# Step-down_converter.net
KiCad netlist of a schematic drawn in Altium Designer
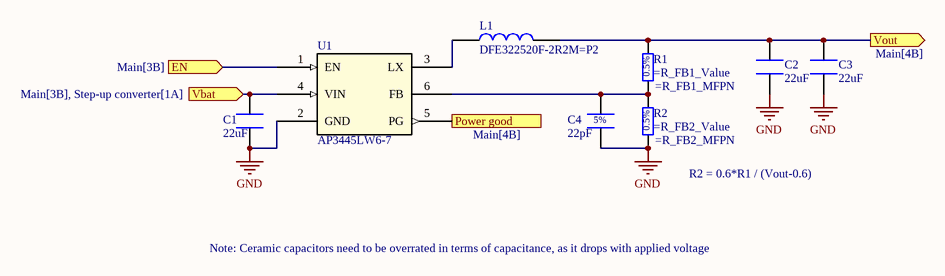
[diagram p0: Step-down converter.SchDoc]

(export (version "E")
  (design (tool "Eeschema 10.0.6"))
  (components
    (comp (ref "C1")
      (value "22uF")
      (footprint "APSS Prototype Parts:CAPACITOR_0805_2012M-70N")
      (description "Passive - Capacitor, X5R, 22uF Max, 6.3V, 0805 (2012 Metric), ±20%, -55°C ~ 85°C. 8.8uF @ 5V")
      (fields (field (name "TOLERANCE") "±20%") (field (name "MF PART NO.") "C0805C226M9PACTU"))
      (libsource (lib "APSS Prototype Parts") (part "C0805C226M9PACTU"))
    )
    (comp (ref "C2")
      (value "22uF")
      (footprint "APSS Prototype Parts:CAPACITOR_0805_2012M-70N")
      (description "Passive - Capacitor, X5R, 22uF Max, 6.3V, 0805 (2012 Metric), ±20%, -55°C ~ 85°C. 8.8uF @ 5V")
      (fields (field (name "TOLERANCE") "±20%") (field (name "MF PART NO.") "C0805C226M9PACTU"))
      (libsource (lib "APSS Prototype Parts") (part "C0805C226M9PACTU"))
    )
    (comp (ref "C3")
      (value "22uF")
      (footprint "APSS Prototype Parts:CAPACITOR_0805_2012M-70N")
      (description "Passive - Capacitor, X5R, 22uF Max, 6.3V, 0805 (2012 Metric), ±20%, -55°C ~ 85°C. 8.8uF @ 5V")
      (fields (field (name "TOLERANCE") "±20%") (field (name "MF PART NO.") "C0805C226M9PACTU"))
      (libsource (lib "APSS Prototype Parts") (part "C0805C226M9PACTU"))
    )
    (comp (ref "C4")
      (value "22pF")
      (footprint "APSS Generic Components:CAPACITOR_0805_2012M-70N")
      (description "Generic Capacitor")
      (fields (field (name "TOLERANCE") "5%") (field (name "MF PART NO.") "C0805C220J5GACTU"))
      (libsource (lib "APSS Generic Components") (part "Generic Capacitor"))
    )
    (comp (ref "L1")
      (value "DFE322520F-2R2M=P2")
      (footprint "INDC3225X200N")
      (description "2.2 uH Shielded Wirewound Inductor 3.3 A 40mOhm Max 1210 (3225 Metric)")
      (libsource (lib "DFE322520F-2R2M=P2") (part "DFE322520F-2R2M=P2"))
    )
    (comp (ref "R1")
      (value "~")
      (footprint "APSS Flight Parts:Resistor_0805_2012M-50N")
      (fields
        (field (name "TOLERANCE") "0.5%")
        (field (name "POWER") "1/8W")
        (field (name "APSS STANDARD PART") "APSS Standard")
      )
      (libsource (lib "APSS Prototype Parts") (part "RG2012P-xxx-D-T5 Series"))
    )
    (comp (ref "R2")
      (value "~")
      (footprint "APSS Flight Parts:Resistor_0805_2012M-50N")
      (fields
        (field (name "TOLERANCE") "0.5%")
        (field (name "POWER") "1/8W")
        (field (name "APSS STANDARD PART") "APSS Standard")
      )
      (libsource (lib "APSS Prototype Parts") (part "RG2012P-xxx-D-T5 Series"))
    )
    (comp (ref "U1")
      (value "AP3445LW6-7")
      (footprint "APSS Prototype Parts:SOT23-6N-1.4mm")
      (description "IC - Regulator, Buck, 2A, 2.7V to 5.5V In, 0.6V to Vin Out, SOT23-6")
      (fields (field (name "APSS STANDARD PART") "APSS Standard"))
      (libsource (lib "APSS Prototype Parts") (part "AP3445LW6-7"))
    )
  )
  (nets
    (net (code "1") (name "/EN") (class "Default")
      (node (ref "U1") (pin "1") (pinfunction "EN_1") (pintype "input"))
    )
    (net (code "2") (name "/Power good") (class "Default")
      (node (ref "U1") (pin "5") (pinfunction "PG_5") (pintype "output"))
    )
    (net (code "3") (name "/Vbat") (class "Default")
      (node (ref "C1") (pin "2") (pinfunction "2_2") (pintype "passive"))
      (node (ref "U1") (pin "4") (pinfunction "VIN_4") (pintype "input"))
    )
    (net (code "4") (name "/Vout") (class "Default")
      (node (ref "C2") (pin "2") (pinfunction "2_2") (pintype "passive"))
      (node (ref "C3") (pin "2") (pinfunction "2_2") (pintype "passive"))
      (node (ref "L1") (pin "1") (pinfunction "1_1") (pintype "passive"))
      (node (ref "R1") (pin "2") (pinfunction "2_2") (pintype "passive"))
    )
    (net (code "5") (name "GND") (class "Default")
      (node (ref "C1") (pin "1") (pinfunction "1_1") (pintype "passive"))
      (node (ref "C2") (pin "1") (pinfunction "1_1") (pintype "passive"))
      (node (ref "C3") (pin "1") (pinfunction "1_1") (pintype "passive"))
      (node (ref "C4") (pin "1") (pinfunction "1_1") (pintype "passive"))
      (node (ref "R2") (pin "1") (pinfunction "1_1") (pintype "passive"))
      (node (ref "U1") (pin "2") (pinfunction "GND_2") (pintype "power_in"))
    )
    (net (code "6") (name "Net-(U1-FB)") (class "Default")
      (node (ref "C4") (pin "2") (pinfunction "2_2") (pintype "passive"))
      (node (ref "R1") (pin "1") (pinfunction "1_1") (pintype "passive"))
      (node (ref "R2") (pin "2") (pinfunction "2_2") (pintype "passive"))
      (node (ref "U1") (pin "6") (pinfunction "FB_6") (pintype "passive"))
    )
    (net (code "7") (name "Net-(U1-LX)") (class "Default")
      (node (ref "L1") (pin "2") (pinfunction "2_2") (pintype "passive"))
      (node (ref "U1") (pin "3") (pinfunction "LX_3") (pintype "passive"))
    )
  )
)
